# DIO_logic.net
KiCad netlist of a schematic drawn in Altium Designer
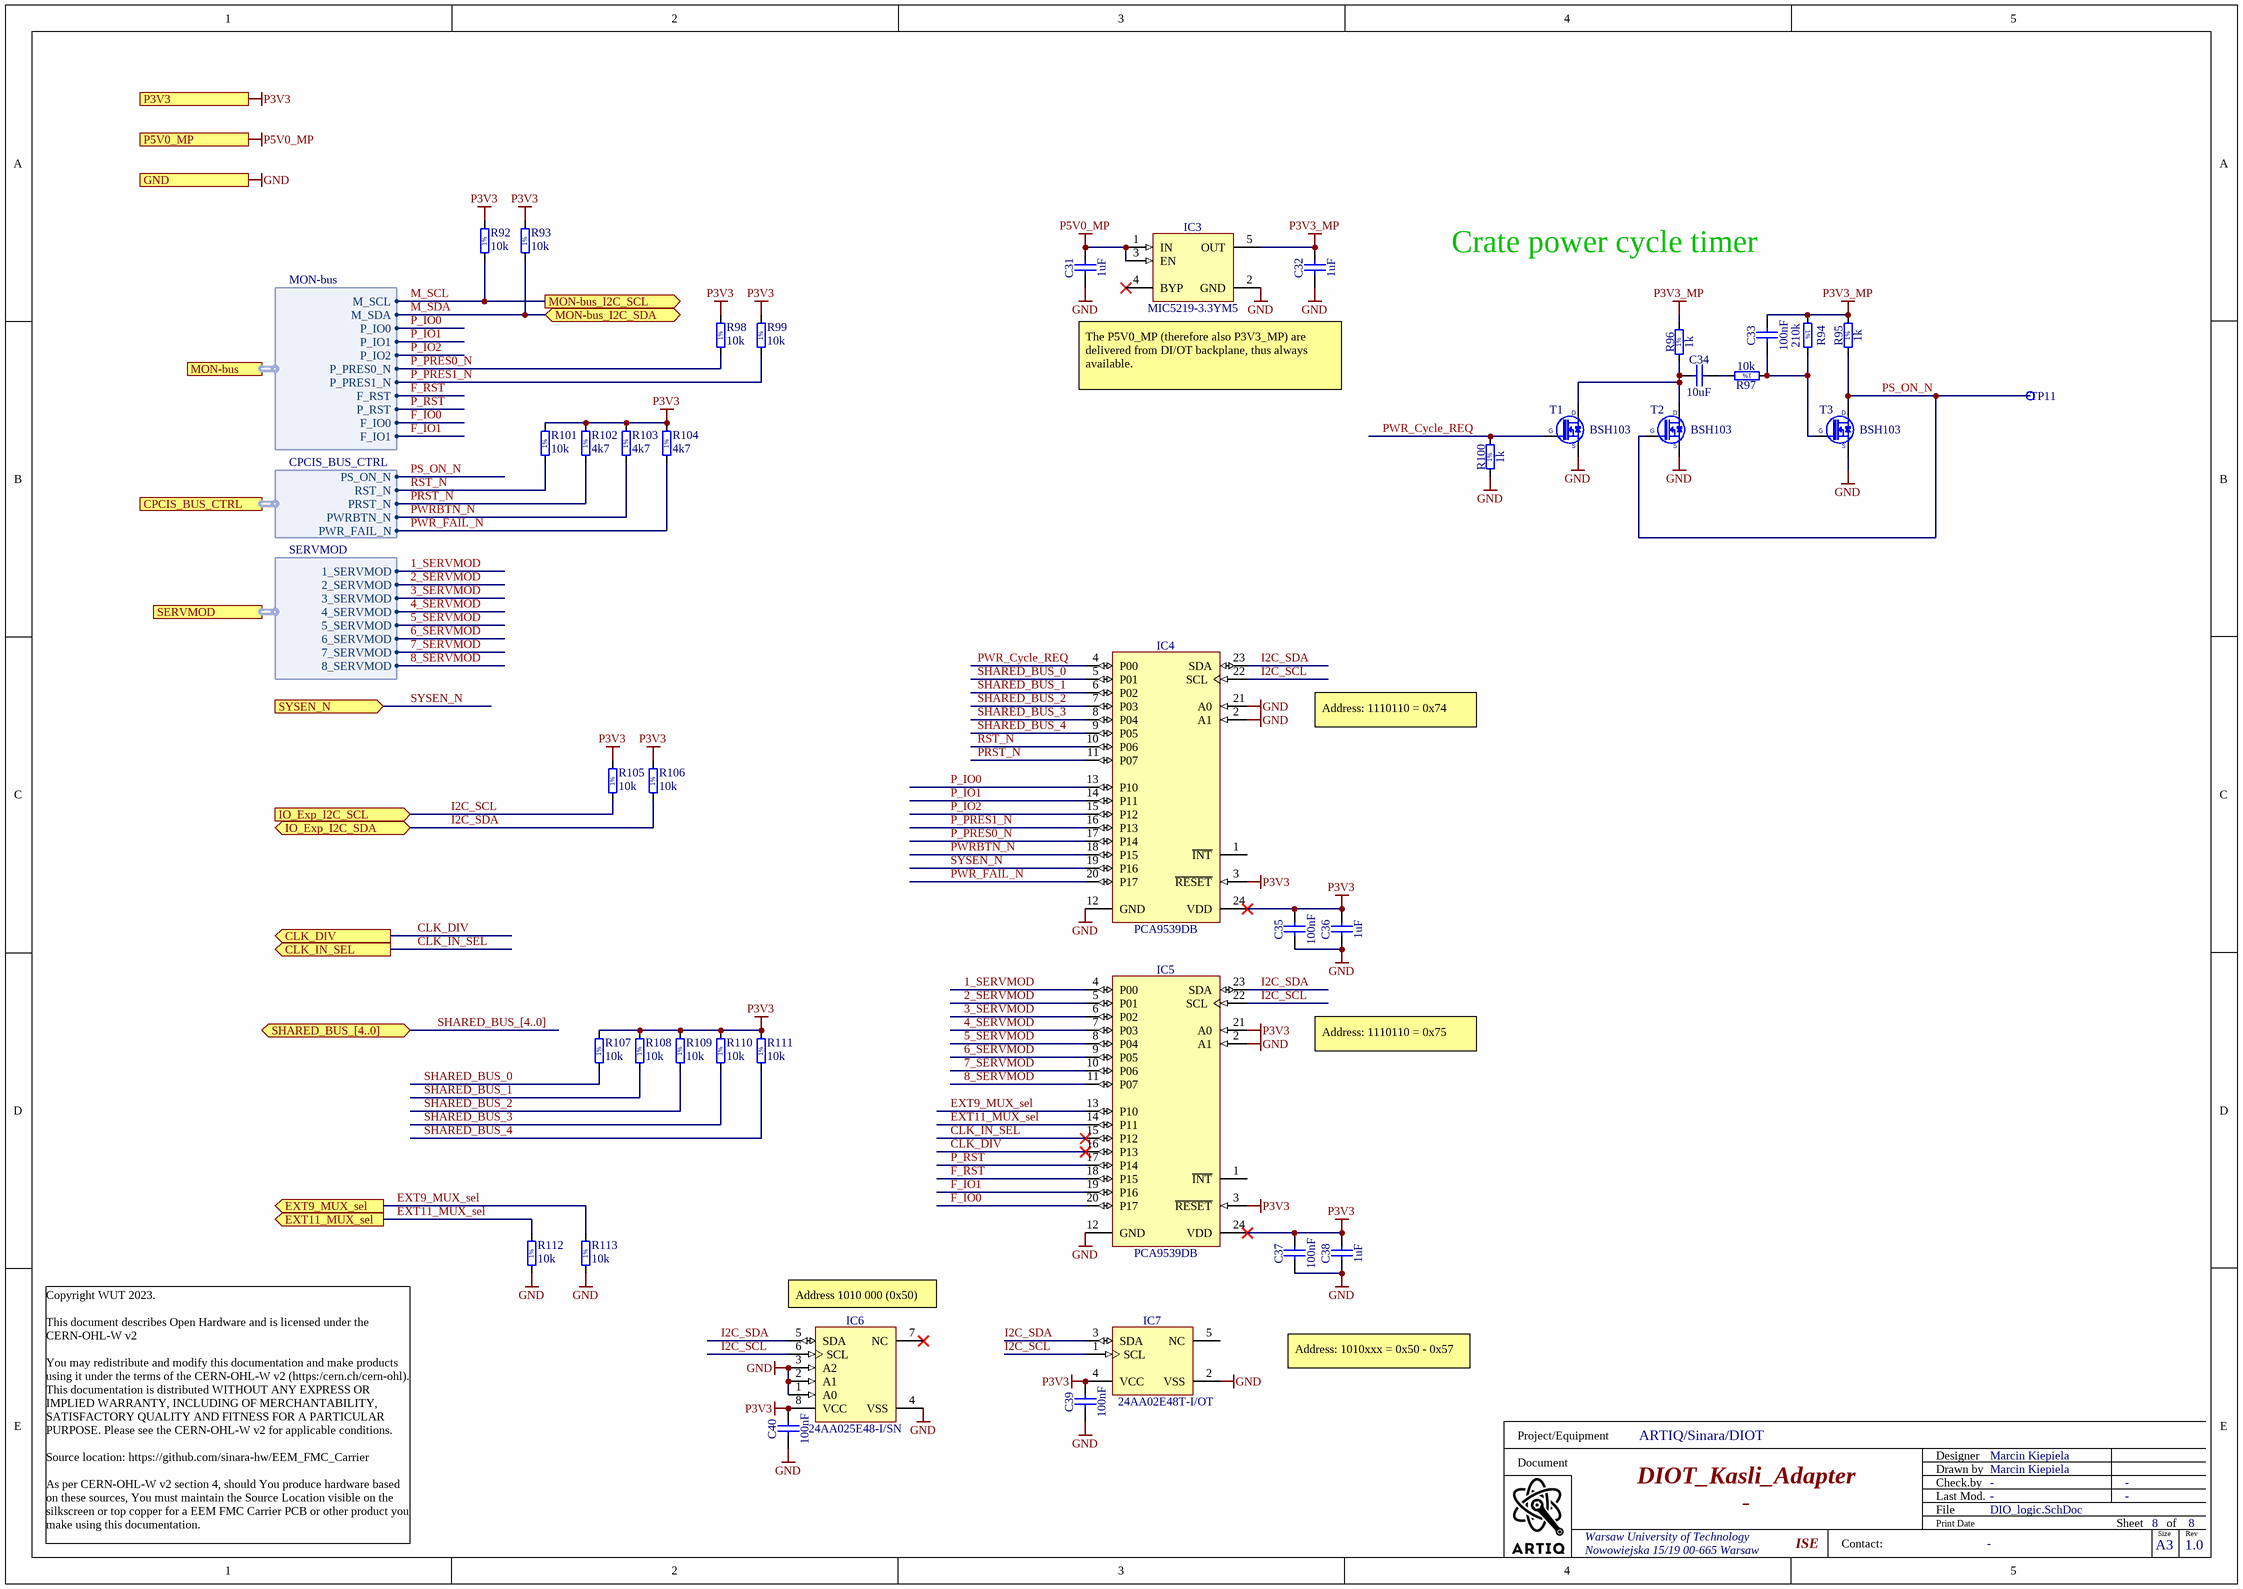
[diagram p0: DIO_logic.SchDoc]

(export (version "E")
  (design (tool "Eeschema 10.0.6"))
  (components
    (comp (ref "C31")
      (value "1uF")
      (footprint "CAPC1608X87N")
      (description "Non-polarised capacitor")
      (fields
        (field (name "PART NUMBER") "CC0603_1UF_25V_10%_X7R")
        (field (name "VOLTAGE") "25V")
        (field (name "AUTHOR") "CERN DEM JLC")
      )
      (libsource (lib "Capacitors") (part "Capacitor - non polarized"))
    )
    (comp (ref "C32")
      (value "1uF")
      (footprint "CAPC1608X87N")
      (description "Non-polarised capacitor")
      (fields
        (field (name "PART NUMBER") "CC0603_1UF_25V_10%_X7R")
        (field (name "VOLTAGE") "25V")
        (field (name "AUTHOR") "CERN DEM JLC")
      )
      (libsource (lib "Capacitors") (part "Capacitor - non polarized"))
    )
    (comp (ref "C33")
      (value "100nF")
      (footprint "CAPC1005X55N")
      (description "Non-polarised capacitor")
      (fields
        (field (name "PART NUMBER") "CC0402_100NF_16V_10%_X7R")
        (field (name "VOLTAGE") "16V")
        (field (name "AUTHOR") "CERN DEM JLC")
      )
      (libsource (lib "Capacitors") (part "Capacitor - non polarized"))
    )
    (comp (ref "C34")
      (value "10uF")
      (footprint "CAPC1608X80N")
      (description "Non-polarised capacitor")
      (fields
        (field (name "PART NUMBER") "CC0603_10UF_10V_10%_X5R")
        (field (name "VOLTAGE") "10V")
        (field (name "AUTHOR") "CERN DEM JLC")
      )
      (libsource (lib "Capacitors") (part "Capacitor - non polarized"))
    )
    (comp (ref "C35")
      (value "100nF")
      (footprint "CAPC1005X55N")
      (description "Non-polarised capacitor")
      (fields
        (field (name "PART NUMBER") "CC0402_100NF_16V_10%_X7R")
        (field (name "VOLTAGE") "16V")
        (field (name "AUTHOR") "CERN DEM JLC")
      )
      (libsource (lib "Capacitors") (part "Capacitor - non polarized"))
    )
    (comp (ref "C36")
      (value "1uF")
      (footprint "CAPC1608X87N")
      (description "Non-polarised capacitor")
      (fields
        (field (name "PART NUMBER") "CC0603_1UF_25V_10%_X7R")
        (field (name "VOLTAGE") "25V")
        (field (name "AUTHOR") "CERN DEM JLC")
      )
      (libsource (lib "Capacitors") (part "Capacitor - non polarized"))
    )
    (comp (ref "C37")
      (value "100nF")
      (footprint "CAPC1005X55N")
      (description "Non-polarised capacitor")
      (fields
        (field (name "PART NUMBER") "CC0402_100NF_16V_10%_X7R")
        (field (name "VOLTAGE") "16V")
        (field (name "AUTHOR") "CERN DEM JLC")
      )
      (libsource (lib "Capacitors") (part "Capacitor - non polarized"))
    )
    (comp (ref "C38")
      (value "1uF")
      (footprint "CAPC1608X87N")
      (description "Non-polarised capacitor")
      (fields
        (field (name "PART NUMBER") "CC0603_1UF_25V_10%_X7R")
        (field (name "VOLTAGE") "25V")
        (field (name "AUTHOR") "CERN DEM JLC")
      )
      (libsource (lib "Capacitors") (part "Capacitor - non polarized"))
    )
    (comp (ref "C39")
      (value "100nF")
      (footprint "CAPC1005X55N")
      (description "Non-polarised capacitor")
      (fields
        (field (name "PART NUMBER") "CC0402_100NF_16V_10%_X7R")
        (field (name "VOLTAGE") "16V")
        (field (name "AUTHOR") "CERN DEM JLC")
      )
      (libsource (lib "Capacitors") (part "Capacitor - non polarized"))
    )
    (comp (ref "C40")
      (value "100nF")
      (footprint "CAPC1005X55N")
      (description "Non-polarised capacitor")
      (fields
        (field (name "PART NUMBER") "CC0402_100NF_16V_10%_X7R")
        (field (name "VOLTAGE") "16V")
        (field (name "AUTHOR") "CERN DEM JLC")
      )
      (libsource (lib "Capacitors") (part "Capacitor - non polarized"))
    )
    (comp (ref "IC3")
      (value "MIC5219-3.3YM5")
      (footprint "SOT95P280X145-5N")
      (description "500mA Peak Output LDO Regulator")
      (fields (field (name "MANUFACTURER") "MICROCHIP TECHNOLOGY") (field (name "AUTHOR") "CERN DEM WB"))
      (libsource (lib "ICs And Semiconductors") (part "MIC5219-X.XYM5"))
    )
    (comp (ref "IC4")
      (value "PCA9539DB")
      (footprint "SOP65P780X200-24N")
      (fields (field (name "MANUFACTURER") "TEXAS INSTRUMENTS") (field (name "AUTHOR") "CERN DEM HF"))
      (libsource (lib "ICs And Semiconductors") (part "PCA9539DB"))
    )
    (comp (ref "IC5")
      (value "PCA9539DB")
      (footprint "SOP65P780X200-24N")
      (fields (field (name "MANUFACTURER") "TEXAS INSTRUMENTS") (field (name "AUTHOR") "CERN DEM HF"))
      (libsource (lib "ICs And Semiconductors") (part "PCA9539DB"))
    )
    (comp (ref "IC6")
      (value "24AA025E48-I/SN")
      (footprint "SOIC127P600X175-8N")
      (description "1.7V-5.5V, 2K I2C™ Serial EEPROMs with EUI-48™ Node Identity")
      (fields (field (name "MANUFACTURER") "MICROCHIP TECHNOLOGY") (field (name "AUTHOR") "CERN DEM MR"))
      (libsource (lib "ICs And Semiconductors") (part "24AA025E48-I/SN"))
    )
    (comp (ref "IC7")
      (value "24AA02E48T-I/OT")
      (footprint "SOT95P280X145-5N")
      (description "1.7V-5.5V, 2K I2C Serial EEPROM With EUI-48 Node Identity")
      (fields (field (name "MANUFACTURER") "MICROCHIP TECHNOLOGY") (field (name "AUTHOR") "CERN DEM MR"))
      (libsource (lib "ICs And Semiconductors") (part "24AA02E48T-I/OT"))
    )
    (comp (ref "R92")
      (value "10k")
      (footprint "RESC1005X40N")
      (description "Resistor - 1%")
      (fields
        (field (name "PART NUMBER") "R0402_10K_1%_0.0625W_100PPM")
        (field (name "POWER") "0.0625W")
        (field (name "AUTHOR") "CERN DEM JLC")
      )
      (libsource (lib "Resistors") (part "Resistor - 1%"))
    )
    (comp (ref "R93")
      (value "10k")
      (footprint "RESC1005X40N")
      (description "Resistor - 1%")
      (fields
        (field (name "PART NUMBER") "R0402_10K_1%_0.0625W_100PPM")
        (field (name "POWER") "0.0625W")
        (field (name "AUTHOR") "CERN DEM JLC")
      )
      (libsource (lib "Resistors") (part "Resistor - 1%"))
    )
    (comp (ref "R94")
      (value "210k")
      (footprint "RESC1005X40N")
      (description "Resistor - 1%")
      (fields
        (field (name "PART NUMBER") "R0402_210k_1%_0.0625W_100PPM")
        (field (name "POWER") "0.0625W")
        (field (name "AUTHOR") "CERN DEM MR")
      )
      (libsource (lib "Resistors") (part "Resistor - 1%"))
    )
    (comp (ref "R95")
      (value "1k")
      (footprint "RESC1005X40N")
      (description "Resistor - 1%")
      (fields
        (field (name "PART NUMBER") "R0402_1K_1%_0.0625W_100PPM")
        (field (name "POWER") "0.0625W")
        (field (name "AUTHOR") "CERN DEM JLC")
      )
      (libsource (lib "Resistors") (part "Resistor - 1%"))
    )
    (comp (ref "R96")
      (value "1k")
      (footprint "RESC1005X40N")
      (description "Resistor - 1%")
      (fields
        (field (name "PART NUMBER") "R0402_1K_1%_0.0625W_100PPM")
        (field (name "POWER") "0.0625W")
        (field (name "AUTHOR") "CERN DEM JLC")
      )
      (libsource (lib "Resistors") (part "Resistor - 1%"))
    )
    (comp (ref "R97")
      (value "10k")
      (footprint "RESC1005X40N")
      (description "Resistor - 1%")
      (fields
        (field (name "PART NUMBER") "R0402_10K_1%_0.0625W_100PPM")
        (field (name "POWER") "0.0625W")
        (field (name "AUTHOR") "CERN DEM JLC")
      )
      (libsource (lib "Resistors") (part "Resistor - 1%"))
    )
    (comp (ref "R98")
      (value "10k")
      (footprint "RESC1005X40N")
      (description "Resistor - 1%")
      (fields
        (field (name "PART NUMBER") "R0402_10K_1%_0.0625W_100PPM")
        (field (name "POWER") "0.0625W")
        (field (name "AUTHOR") "CERN DEM JLC")
      )
      (libsource (lib "Resistors") (part "Resistor - 1%"))
    )
    (comp (ref "R99")
      (value "10k")
      (footprint "RESC1005X40N")
      (description "Resistor - 1%")
      (fields
        (field (name "PART NUMBER") "R0402_10K_1%_0.0625W_100PPM")
        (field (name "POWER") "0.0625W")
        (field (name "AUTHOR") "CERN DEM JLC")
      )
      (libsource (lib "Resistors") (part "Resistor - 1%"))
    )
    (comp (ref "R100")
      (value "1k")
      (footprint "RESC1005X40N")
      (description "Resistor - 1%")
      (fields
        (field (name "PART NUMBER") "R0402_1K_1%_0.0625W_100PPM")
        (field (name "POWER") "0.0625W")
        (field (name "AUTHOR") "CERN DEM JLC")
      )
      (libsource (lib "Resistors") (part "Resistor - 1%"))
    )
    (comp (ref "R101")
      (value "10k")
      (footprint "RESC1005X40N")
      (description "Resistor - 1%")
      (fields
        (field (name "PART NUMBER") "R0402_10K_1%_0.0625W_100PPM")
        (field (name "POWER") "0.0625W")
        (field (name "AUTHOR") "CERN DEM JLC")
      )
      (libsource (lib "Resistors") (part "Resistor - 1%"))
    )
    (comp (ref "R102")
      (value "4k7")
      (footprint "RESC1005X40N")
      (description "Resistor - 1%")
      (fields
        (field (name "PART NUMBER") "R0402_4K7_1%_0.0625W_100PPM")
        (field (name "POWER") "0.0625W")
        (field (name "AUTHOR") "CERN DEM JLC")
      )
      (libsource (lib "Resistors") (part "Resistor - 1%"))
    )
    (comp (ref "R103")
      (value "4k7")
      (footprint "RESC1005X40N")
      (description "Resistor - 1%")
      (fields
        (field (name "PART NUMBER") "R0402_4K7_1%_0.0625W_100PPM")
        (field (name "POWER") "0.0625W")
        (field (name "AUTHOR") "CERN DEM JLC")
      )
      (libsource (lib "Resistors") (part "Resistor - 1%"))
    )
    (comp (ref "R104")
      (value "4k7")
      (footprint "RESC1005X40N")
      (description "Resistor - 1%")
      (fields
        (field (name "PART NUMBER") "R0402_4K7_1%_0.0625W_100PPM")
        (field (name "POWER") "0.0625W")
        (field (name "AUTHOR") "CERN DEM JLC")
      )
      (libsource (lib "Resistors") (part "Resistor - 1%"))
    )
    (comp (ref "R105")
      (value "10k")
      (footprint "RESC1005X40N")
      (description "Resistor - 1%")
      (fields
        (field (name "PART NUMBER") "R0402_10K_1%_0.0625W_100PPM")
        (field (name "POWER") "0.0625W")
        (field (name "AUTHOR") "CERN DEM JLC")
      )
      (libsource (lib "Resistors") (part "Resistor - 1%"))
    )
    (comp (ref "R106")
      (value "10k")
      (footprint "RESC1005X40N")
      (description "Resistor - 1%")
      (fields
        (field (name "PART NUMBER") "R0402_10K_1%_0.0625W_100PPM")
        (field (name "POWER") "0.0625W")
        (field (name "AUTHOR") "CERN DEM JLC")
      )
      (libsource (lib "Resistors") (part "Resistor - 1%"))
    )
    (comp (ref "R107")
      (value "10k")
      (footprint "RESC1005X40N")
      (description "Resistor - 1%")
      (fields
        (field (name "PART NUMBER") "R0402_10K_1%_0.0625W_100PPM")
        (field (name "POWER") "0.0625W")
        (field (name "AUTHOR") "CERN DEM JLC")
      )
      (libsource (lib "Resistors") (part "Resistor - 1%"))
    )
    (comp (ref "R108")
      (value "10k")
      (footprint "RESC1005X40N")
      (description "Resistor - 1%")
      (fields
        (field (name "PART NUMBER") "R0402_10K_1%_0.0625W_100PPM")
        (field (name "POWER") "0.0625W")
        (field (name "AUTHOR") "CERN DEM JLC")
      )
      (libsource (lib "Resistors") (part "Resistor - 1%"))
    )
    (comp (ref "R109")
      (value "10k")
      (footprint "RESC1005X40N")
      (description "Resistor - 1%")
      (fields
        (field (name "PART NUMBER") "R0402_10K_1%_0.0625W_100PPM")
        (field (name "POWER") "0.0625W")
        (field (name "AUTHOR") "CERN DEM JLC")
      )
      (libsource (lib "Resistors") (part "Resistor - 1%"))
    )
    (comp (ref "R110")
      (value "10k")
      (footprint "RESC1005X40N")
      (description "Resistor - 1%")
      (fields
        (field (name "PART NUMBER") "R0402_10K_1%_0.0625W_100PPM")
        (field (name "POWER") "0.0625W")
        (field (name "AUTHOR") "CERN DEM JLC")
      )
      (libsource (lib "Resistors") (part "Resistor - 1%"))
    )
    (comp (ref "R111")
      (value "10k")
      (footprint "RESC1005X40N")
      (description "Resistor - 1%")
      (fields
        (field (name "PART NUMBER") "R0402_10K_1%_0.0625W_100PPM")
        (field (name "POWER") "0.0625W")
        (field (name "AUTHOR") "CERN DEM JLC")
      )
      (libsource (lib "Resistors") (part "Resistor - 1%"))
    )
    (comp (ref "R112")
      (value "10k")
      (footprint "RESC1005X40N")
      (description "Resistor - 1%")
      (fields
        (field (name "PART NUMBER") "R0402_10K_1%_0.0625W_100PPM")
        (field (name "POWER") "0.0625W")
        (field (name "AUTHOR") "CERN DEM JLC")
      )
      (libsource (lib "Resistors") (part "Resistor - 1%"))
    )
    (comp (ref "R113")
      (value "10k")
      (footprint "RESC1005X40N")
      (description "Resistor - 1%")
      (fields
        (field (name "PART NUMBER") "R0402_10K_1%_0.0625W_100PPM")
        (field (name "POWER") "0.0625W")
        (field (name "AUTHOR") "CERN DEM JLC")
      )
      (libsource (lib "Resistors") (part "Resistor - 1%"))
    )
    (comp (ref "T1")
      (value "BSH103")
      (footprint "SOT95P230X110-3N")
      (description "N-CHANNEL MOSFET WITH DIODE")
      (fields (field (name "MANUFACTURER") "NEXPERIA") (field (name "AUTHOR") "CERN DEM JLC"))
      (libsource (lib "ICs And Semiconductors") (part "N-MOSFET-D 1G 2S 3D"))
    )
    (comp (ref "T2")
      (value "BSH103")
      (footprint "SOT95P230X110-3N")
      (description "N-CHANNEL MOSFET WITH DIODE")
      (fields (field (name "MANUFACTURER") "NEXPERIA") (field (name "AUTHOR") "CERN DEM JLC"))
      (libsource (lib "ICs And Semiconductors") (part "N-MOSFET-D 1G 2S 3D"))
    )
    (comp (ref "T3")
      (value "BSH103")
      (footprint "SOT95P230X110-3N")
      (description "N-CHANNEL MOSFET WITH DIODE")
      (fields (field (name "MANUFACTURER") "NEXPERIA") (field (name "AUTHOR") "CERN DEM JLC"))
      (libsource (lib "ICs And Semiconductors") (part "N-MOSFET-D 1G 2S 3D"))
    )
    (comp (ref "TP11")
      (value "P3V3")
      (footprint "TPS127")
      (description "Test Point")
      (fields (field (name "PART NUMBER") "SMD_PAD_1.27X1.27MM") (field (name "AUTHOR") "CERN DEM JLC"))
      (libsource (lib "Eletro-mechanical") (part "Test Point"))
    )
  )
  (nets
    (net (code "4") (name "/1_SERVMOD") (class "Default")
      (node (ref "IC5") (pin "4") (pinfunction "P00_4") (pintype "bidirectional"))
    )
    (net (code "5") (name "/2_SERVMOD") (class "Default")
      (node (ref "IC5") (pin "5") (pinfunction "P01_5") (pintype "bidirectional"))
    )
    (net (code "6") (name "/3_SERVMOD") (class "Default")
      (node (ref "IC5") (pin "6") (pinfunction "P02_6") (pintype "bidirectional"))
    )
    (net (code "7") (name "/4_SERVMOD") (class "Default")
      (node (ref "IC5") (pin "7") (pinfunction "P03_7") (pintype "bidirectional"))
    )
    (net (code "8") (name "/5_SERVMOD") (class "Default")
      (node (ref "IC5") (pin "8") (pinfunction "P04_8") (pintype "bidirectional"))
    )
    (net (code "9") (name "/6_SERVMOD") (class "Default")
      (node (ref "IC5") (pin "9") (pinfunction "P05_9") (pintype "bidirectional"))
    )
    (net (code "10") (name "/7_SERVMOD") (class "Default")
      (node (ref "IC5") (pin "10") (pinfunction "P06_10") (pintype "bidirectional"))
    )
    (net (code "11") (name "/8_SERVMOD") (class "Default")
      (node (ref "IC5") (pin "11") (pinfunction "P07_11") (pintype "bidirectional"))
    )
    (net (code "12") (name "/CLK_DIV") (class "Default")
      (node (ref "IC5") (pin "16") (pinfunction "P13_16") (pintype "bidirectional+no_connect"))
    )
    (net (code "13") (name "/CLK_IN_SEL") (class "Default")
      (node (ref "IC5") (pin "15") (pinfunction "P12_15") (pintype "bidirectional+no_connect"))
    )
    (net (code "14") (name "/EXT9_MUX_sel") (class "Default")
      (node (ref "IC5") (pin "13") (pinfunction "P10_13") (pintype "bidirectional"))
      (node (ref "R113") (pin "2") (pinfunction "2_2") (pintype "passive"))
    )
    (net (code "15") (name "/EXT11_MUX_sel") (class "Default")
      (node (ref "IC5") (pin "14") (pinfunction "P11_14") (pintype "bidirectional"))
      (node (ref "R112") (pin "2") (pinfunction "2_2") (pintype "passive"))
    )
    (net (code "16") (name "/F_IO0") (class "Default")
      (node (ref "IC5") (pin "20") (pinfunction "P17_20") (pintype "bidirectional"))
    )
    (net (code "17") (name "/F_IO1") (class "Default")
      (node (ref "IC5") (pin "19") (pinfunction "P16_19") (pintype "bidirectional"))
    )
    (net (code "18") (name "/F_RST") (class "Default")
      (node (ref "IC5") (pin "18") (pinfunction "P15_18") (pintype "bidirectional"))
    )
    (net (code "19") (name "/I2C_SCL") (class "Default")
      (node (ref "IC4") (pin "22") (pinfunction "SCL_22") (pintype "input"))
      (node (ref "IC5") (pin "22") (pinfunction "SCL_22") (pintype "input"))
      (node (ref "IC6") (pin "6") (pinfunction "SCL_6") (pintype "input"))
      (node (ref "IC7") (pin "1") (pinfunction "SCL_1") (pintype "input"))
      (node (ref "R105") (pin "1") (pinfunction "1_1") (pintype "passive"))
    )
    (net (code "20") (name "/I2C_SDA") (class "Default")
      (node (ref "IC4") (pin "23") (pinfunction "SDA_23") (pintype "bidirectional"))
      (node (ref "IC5") (pin "23") (pinfunction "SDA_23") (pintype "bidirectional"))
      (node (ref "IC6") (pin "5") (pinfunction "SDA_5") (pintype "bidirectional"))
      (node (ref "IC7") (pin "3") (pinfunction "SDA_3") (pintype "bidirectional"))
      (node (ref "R106") (pin "1") (pinfunction "1_1") (pintype "passive"))
    )
    (net (code "21") (name "/M_SCL") (class "Default")
      (node (ref "R92") (pin "1") (pinfunction "1_1") (pintype "passive"))
    )
    (net (code "22") (name "/M_SDA") (class "Default")
      (node (ref "R93") (pin "1") (pinfunction "1_1") (pintype "passive"))
    )
    (net (code "23") (name "/PRST_N") (class "Default")
      (node (ref "IC4") (pin "11") (pinfunction "P07_11") (pintype "bidirectional"))
      (node (ref "R102") (pin "1") (pinfunction "1_1") (pintype "passive"))
    )
    (net (code "24") (name "/PS_ON_N") (class "Default")
      (node (ref "R95") (pin "1") (pinfunction "1_1") (pintype "passive"))
      (node (ref "T2") (pin "1") (pinfunction "G_1") (pintype "passive"))
      (node (ref "T3") (pin "3") (pinfunction "D_3") (pintype "passive"))
      (node (ref "TP11") (pin "1") (pinfunction "1_1") (pintype "bidirectional"))
    )
    (net (code "25") (name "/PWRBTN_N") (class "Default")
      (node (ref "IC4") (pin "18") (pinfunction "P15_18") (pintype "bidirectional"))
      (node (ref "R103") (pin "1") (pinfunction "1_1") (pintype "passive"))
    )
    (net (code "26") (name "/PWR_Cycle_REQ") (class "Default")
      (node (ref "IC4") (pin "4") (pinfunction "P00_4") (pintype "bidirectional"))
      (node (ref "R100") (pin "2") (pinfunction "2_2") (pintype "passive"))
      (node (ref "T1") (pin "1") (pinfunction "G_1") (pintype "passive"))
    )
    (net (code "27") (name "/PWR_FAIL_N") (class "Default")
      (node (ref "IC4") (pin "20") (pinfunction "P17_20") (pintype "bidirectional"))
      (node (ref "R104") (pin "1") (pinfunction "1_1") (pintype "passive"))
    )
    (net (code "28") (name "/P_IO0") (class "Default")
      (node (ref "IC4") (pin "13") (pinfunction "P10_13") (pintype "bidirectional"))
    )
    (net (code "29") (name "/P_IO1") (class "Default")
      (node (ref "IC4") (pin "14") (pinfunction "P11_14") (pintype "bidirectional"))
    )
    (net (code "30") (name "/P_IO2") (class "Default")
      (node (ref "IC4") (pin "15") (pinfunction "P12_15") (pintype "bidirectional"))
    )
    (net (code "31") (name "/P_PRES0_N") (class "Default")
      (node (ref "IC4") (pin "17") (pinfunction "P14_17") (pintype "bidirectional"))
      (node (ref "R98") (pin "1") (pinfunction "1_1") (pintype "passive"))
    )
    (net (code "32") (name "/P_PRES1_N") (class "Default")
      (node (ref "IC4") (pin "16") (pinfunction "P13_16") (pintype "bidirectional"))
      (node (ref "R99") (pin "1") (pinfunction "1_1") (pintype "passive"))
    )
    (net (code "33") (name "/P_RST") (class "Default")
      (node (ref "IC5") (pin "17") (pinfunction "P14_17") (pintype "bidirectional"))
    )
    (net (code "34") (name "/RST_N") (class "Default")
      (node (ref "IC4") (pin "10") (pinfunction "P06_10") (pintype "bidirectional"))
      (node (ref "R101") (pin "1") (pinfunction "1_1") (pintype "passive"))
    )
    (net (code "35") (name "/SHARED_BUS_0") (class "Default")
      (node (ref "IC4") (pin "5") (pinfunction "P01_5") (pintype "bidirectional"))
      (node (ref "R107") (pin "1") (pinfunction "1_1") (pintype "passive"))
    )
    (net (code "36") (name "/SHARED_BUS_1") (class "Default")
      (node (ref "IC4") (pin "6") (pinfunction "P02_6") (pintype "bidirectional"))
      (node (ref "R108") (pin "1") (pinfunction "1_1") (pintype "passive"))
    )
    (net (code "37") (name "/SHARED_BUS_2") (class "Default")
      (node (ref "IC4") (pin "7") (pinfunction "P03_7") (pintype "bidirectional"))
      (node (ref "R109") (pin "1") (pinfunction "1_1") (pintype "passive"))
    )
    (net (code "38") (name "/SHARED_BUS_3") (class "Default")
      (node (ref "IC4") (pin "8") (pinfunction "P04_8") (pintype "bidirectional"))
      (node (ref "R110") (pin "1") (pinfunction "1_1") (pintype "passive"))
    )
    (net (code "39") (name "/SHARED_BUS_4") (class "Default")
      (node (ref "IC4") (pin "9") (pinfunction "P05_9") (pintype "bidirectional"))
      (node (ref "R111") (pin "1") (pinfunction "1_1") (pintype "passive"))
    )
    (net (code "41") (name "/SYSEN_N") (class "Default")
      (node (ref "IC4") (pin "19") (pinfunction "P16_19") (pintype "bidirectional"))
    )
    (net (code "45") (name "GND") (class "Default")
      (node (ref "C31") (pin "1") (pinfunction "1_1") (pintype "passive"))
      (node (ref "C32") (pin "1") (pinfunction "1_1") (pintype "passive"))
      (node (ref "C35") (pin "1") (pinfunction "1_1") (pintype "passive"))
      (node (ref "C36") (pin "1") (pinfunction "1_1") (pintype "passive"))
      (node (ref "C37") (pin "1") (pinfunction "1_1") (pintype "passive"))
      (node (ref "C38") (pin "1") (pinfunction "1_1") (pintype "passive"))
      (node (ref "C39") (pin "1") (pinfunction "1_1") (pintype "passive"))
      (node (ref "C40") (pin "1") (pinfunction "1_1") (pintype "passive"))
      (node (ref "IC3") (pin "2") (pinfunction "GND_2") (pintype "power_in"))
      (node (ref "IC4") (pin "12") (pinfunction "GND_12") (pintype "power_in"))
      (node (ref "IC4") (pin "2") (pinfunction "A1_2") (pintype "input"))
      (node (ref "IC4") (pin "21") (pinfunction "A0_21") (pintype "input"))
      (node (ref "IC5") (pin "12") (pinfunction "GND_12") (pintype "power_in"))
      (node (ref "IC5") (pin "2") (pinfunction "A1_2") (pintype "input"))
      (node (ref "IC6") (pin "1") (pinfunction "A0_1") (pintype "input"))
      (node (ref "IC6") (pin "2") (pinfunction "A1_2") (pintype "input"))
      (node (ref "IC6") (pin "3") (pinfunction "A2_3") (pintype "input"))
      (node (ref "IC6") (pin "4") (pinfunction "VSS_4") (pintype "power_in"))
      (node (ref "IC7") (pin "2") (pinfunction "VSS_2") (pintype "power_in"))
      (node (ref "R100") (pin "1") (pinfunction "1_1") (pintype "passive"))
      (node (ref "R112") (pin "1") (pinfunction "1_1") (pintype "passive"))
      (node (ref "R113") (pin "1") (pinfunction "1_1") (pintype "passive"))
      (node (ref "T1") (pin "2") (pinfunction "S_2") (pintype "passive"))
      (node (ref "T2") (pin "2") (pinfunction "S_2") (pintype "passive"))
      (node (ref "T3") (pin "2") (pinfunction "S_2") (pintype "passive"))
    )
    (net (code "46") (name "Net-(C34-Pad2)") (class "Default")
      (node (ref "C34") (pin "2") (pinfunction "2_2") (pintype "passive"))
      (node (ref "R97") (pin "2") (pinfunction "2_2") (pintype "passive"))
    )
    (net (code "47") (name "Net-(T1-D)") (class "Default")
      (node (ref "C34") (pin "1") (pinfunction "1_1") (pintype "passive"))
      (node (ref "R96") (pin "1") (pinfunction "1_1") (pintype "passive"))
      (node (ref "T1") (pin "3") (pinfunction "D_3") (pintype "passive"))
      (node (ref "T2") (pin "3") (pinfunction "D_3") (pintype "passive"))
    )
    (net (code "48") (name "Net-(T3-G)") (class "Default")
      (node (ref "C33") (pin "1") (pinfunction "1_1") (pintype "passive"))
      (node (ref "R94") (pin "2") (pinfunction "2_2") (pintype "passive"))
      (node (ref "R97") (pin "1") (pinfunction "1_1") (pintype "passive"))
      (node (ref "T3") (pin "1") (pinfunction "G_1") (pintype "passive"))
    )
    (net (code "49") (name "P3V3") (class "Default")
      (node (ref "C35") (pin "2") (pinfunction "2_2") (pintype "passive"))
      (node (ref "C36") (pin "2") (pinfunction "2_2") (pintype "passive"))
      (node (ref "C37") (pin "2") (pinfunction "2_2") (pintype "passive"))
      (node (ref "C38") (pin "2") (pinfunction "2_2") (pintype "passive"))
      (node (ref "C39") (pin "2") (pinfunction "2_2") (pintype "passive"))
      (node (ref "C40") (pin "2") (pinfunction "2_2") (pintype "passive"))
      (node (ref "IC4") (pin "24") (pinfunction "VDD_24") (pintype "power_in"))
      (node (ref "IC4") (pin "3") (pinfunction "~{RESET}_3") (pintype "input"))
      (node (ref "IC5") (pin "21") (pinfunction "A0_21") (pintype "input"))
      (node (ref "IC5") (pin "24") (pinfunction "VDD_24") (pintype "power_in"))
      (node (ref "IC5") (pin "3") (pinfunction "~{RESET}_3") (pintype "input"))
      (node (ref "IC6") (pin "8") (pinfunction "VCC_8") (pintype "power_in"))
      (node (ref "IC7") (pin "4") (pinfunction "VCC_4") (pintype "power_in"))
      (node (ref "R101") (pin "2") (pinfunction "2_2") (pintype "passive"))
      (node (ref "R102") (pin "2") (pinfunction "2_2") (pintype "passive"))
      (node (ref "R103") (pin "2") (pinfunction "2_2") (pintype "passive"))
      (node (ref "R104") (pin "2") (pinfunction "2_2") (pintype "passive"))
      (node (ref "R105") (pin "2") (pinfunction "2_2") (pintype "passive"))
      (node (ref "R106") (pin "2") (pinfunction "2_2") (pintype "passive"))
      (node (ref "R107") (pin "2") (pinfunction "2_2") (pintype "passive"))
      (node (ref "R108") (pin "2") (pinfunction "2_2") (pintype "passive"))
      (node (ref "R109") (pin "2") (pinfunction "2_2") (pintype "passive"))
      (node (ref "R110") (pin "2") (pinfunction "2_2") (pintype "passive"))
      (node (ref "R111") (pin "2") (pinfunction "2_2") (pintype "passive"))
      (node (ref "R92") (pin "2") (pinfunction "2_2") (pintype "passive"))
      (node (ref "R93") (pin "2") (pinfunction "2_2") (pintype "passive"))
      (node (ref "R98") (pin "2") (pinfunction "2_2") (pintype "passive"))
      (node (ref "R99") (pin "2") (pinfunction "2_2") (pintype "passive"))
    )
    (net (code "50") (name "P3V3_MP") (class "Default")
      (node (ref "C32") (pin "2") (pinfunction "2_2") (pintype "passive"))
      (node (ref "C33") (pin "2") (pinfunction "2_2") (pintype "passive"))
      (node (ref "IC3") (pin "5") (pinfunction "OUT_5") (pintype "power_in"))
      (node (ref "R94") (pin "1") (pinfunction "1_1") (pintype "passive"))
      (node (ref "R95") (pin "2") (pinfunction "2_2") (pintype "passive"))
      (node (ref "R96") (pin "2") (pinfunction "2_2") (pintype "passive"))
    )
    (net (code "51") (name "P5V0_MP") (class "Default")
      (node (ref "C31") (pin "2") (pinfunction "2_2") (pintype "passive"))
      (node (ref "IC3") (pin "1") (pinfunction "IN_1") (pintype "input"))
      (node (ref "IC3") (pin "3") (pinfunction "EN_3") (pintype "input"))
    )
    (net (code "52") (name "unconnected-(IC3-BYP-Pad4)") (class "Default")
      (node (ref "IC3") (pin "4") (pinfunction "BYP_4") (pintype "passive+no_connect"))
    )
    (net (code "53") (name "unconnected-(IC4-~{INT}-Pad1)") (class "Default")
      (node (ref "IC4") (pin "1") (pinfunction "~{INT}_1") (pintype "open_collector"))
    )
    (net (code "54") (name "unconnected-(IC5-~{INT}-Pad1)") (class "Default")
      (node (ref "IC5") (pin "1") (pinfunction "~{INT}_1") (pintype "open_collector"))
    )
    (net (code "55") (name "unconnected-(IC6-NC-Pad7)") (class "Default")
      (node (ref "IC6") (pin "7") (pinfunction "NC_7") (pintype "passive+no_connect"))
    )
    (net (code "56") (name "unconnected-(IC7-NC-Pad5)") (class "Default")
      (node (ref "IC7") (pin "5") (pinfunction "NC_5") (pintype "passive"))
    )
  )
)
